# 4-IN-OPTPO-4-OUT-B.net
KiCad netlist of a schematic drawn in EAGLE
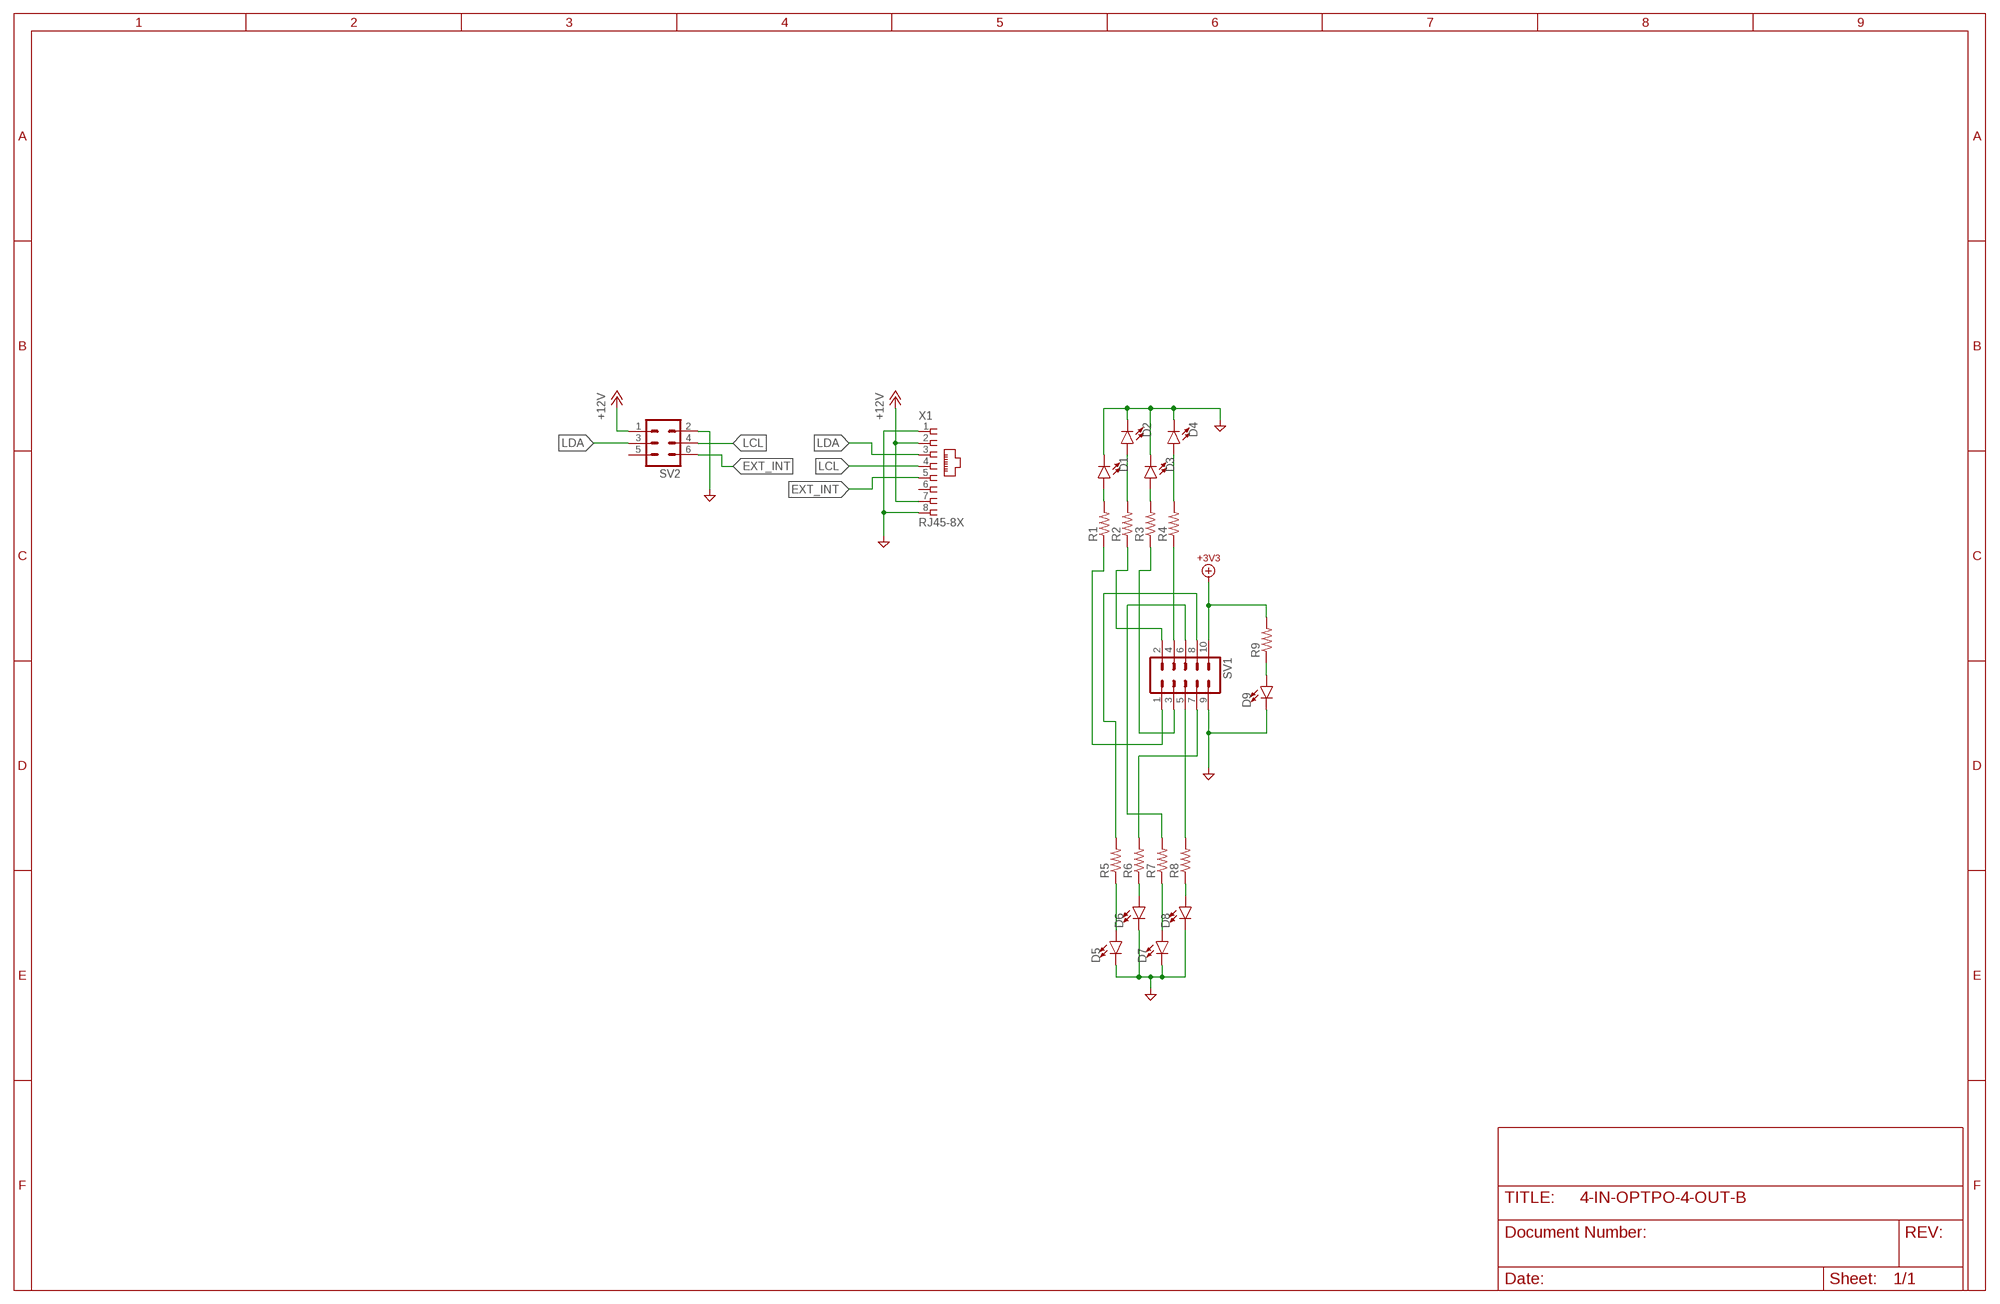
[diagram p0: schematic, sheet 1]

(export (version "E")
  (design (tool "Eeschema 10.0.6"))
  (components
    (comp (ref "D1")
      (value "LED3MM")
      (footprint "eagle-import:LED_3MM")
      (libsource (lib "eagle-import") (part "LED3MM"))
    )
    (comp (ref "D2")
      (value "LED3MM")
      (footprint "eagle-import:LED_3MM")
      (libsource (lib "eagle-import") (part "LED3MM"))
    )
    (comp (ref "D3")
      (value "LED3MM")
      (footprint "eagle-import:LED_3MM")
      (libsource (lib "eagle-import") (part "LED3MM"))
    )
    (comp (ref "D4")
      (value "LED3MM")
      (footprint "eagle-import:LED_3MM")
      (libsource (lib "eagle-import") (part "LED3MM"))
    )
    (comp (ref "D5")
      (value "LED3MM")
      (footprint "eagle-import:LED_3MM")
      (libsource (lib "eagle-import") (part "LED3MM"))
    )
    (comp (ref "D6")
      (value "LED3MM")
      (footprint "eagle-import:LED_3MM")
      (libsource (lib "eagle-import") (part "LED3MM"))
    )
    (comp (ref "D7")
      (value "LED3MM")
      (footprint "eagle-import:LED_3MM")
      (libsource (lib "eagle-import") (part "LED3MM"))
    )
    (comp (ref "D8")
      (value "LED3MM")
      (footprint "eagle-import:LED_3MM")
      (libsource (lib "eagle-import") (part "LED3MM"))
    )
    (comp (ref "D9")
      (value "LED3MM")
      (footprint "eagle-import:LED_3MM")
      (libsource (lib "eagle-import") (part "LED3MM"))
    )
    (comp (ref "R1")
      (value "R-US_R0805")
      (footprint "eagle-import:R0805")
      (libsource (lib "eagle-import") (part "R-US_R0805"))
    )
    (comp (ref "R2")
      (value "R-US_R0805")
      (footprint "eagle-import:R0805")
      (libsource (lib "eagle-import") (part "R-US_R0805"))
    )
    (comp (ref "R3")
      (value "R-US_R0805")
      (footprint "eagle-import:R0805")
      (libsource (lib "eagle-import") (part "R-US_R0805"))
    )
    (comp (ref "R4")
      (value "R-US_R0805")
      (footprint "eagle-import:R0805")
      (libsource (lib "eagle-import") (part "R-US_R0805"))
    )
    (comp (ref "R5")
      (value "R-US_R0805")
      (footprint "eagle-import:R0805")
      (libsource (lib "eagle-import") (part "R-US_R0805"))
    )
    (comp (ref "R6")
      (value "R-US_R0805")
      (footprint "eagle-import:R0805")
      (libsource (lib "eagle-import") (part "R-US_R0805"))
    )
    (comp (ref "R7")
      (value "R-US_R0805")
      (footprint "eagle-import:R0805")
      (libsource (lib "eagle-import") (part "R-US_R0805"))
    )
    (comp (ref "R8")
      (value "R-US_R0805")
      (footprint "eagle-import:R0805")
      (libsource (lib "eagle-import") (part "R-US_R0805"))
    )
    (comp (ref "R9")
      (value "R-US_R0805")
      (footprint "eagle-import:R0805")
      (libsource (lib "eagle-import") (part "R-US_R0805"))
    )
    (comp (ref "SV1")
      (value "ML10")
      (footprint "eagle-import:ML10")
      (libsource (lib "eagle-import") (part "ML10"))
    )
    (comp (ref "SV2")
      (value "ML6")
      (footprint "eagle-import:ML6")
      (libsource (lib "eagle-import") (part "ML6"))
    )
    (comp (ref "X1")
      (value "RJ45-8X")
      (footprint "eagle-import:RJ45-NO-SHIELD")
      (libsource (lib "eagle-import") (part "RJ45-8X"))
    )
  )
  (nets
    (net (code "1") (name "+12V") (class "Default")
      (node (ref "SV2") (pin "1") (pinfunction "1_1") (pintype "passive"))
      (node (ref "X1") (pin "2") (pinfunction "2_2") (pintype "passive"))
      (node (ref "X1") (pin "7") (pinfunction "7_7") (pintype "passive"))
    )
    (net (code "2") (name "EXT_INT") (class "Default")
      (node (ref "SV2") (pin "6") (pinfunction "6_6") (pintype "passive"))
      (node (ref "X1") (pin "5") (pinfunction "5_5") (pintype "passive"))
    )
    (net (code "3") (name "LCL") (class "Default")
      (node (ref "SV2") (pin "4") (pinfunction "4_4") (pintype "passive"))
      (node (ref "X1") (pin "4") (pinfunction "4_4") (pintype "passive"))
    )
    (net (code "4") (name "LDA") (class "Default")
      (node (ref "SV2") (pin "3") (pinfunction "3_3") (pintype "passive"))
      (node (ref "X1") (pin "3") (pinfunction "3_3") (pintype "passive"))
    )
    (net (code "5") (name "Net-(D1-PadA)") (class "Default")
      (node (ref "D1") (pin "A") (pinfunction "A_A") (pintype "passive"))
      (node (ref "R1") (pin "2") (pinfunction "2_2") (pintype "passive"))
    )
    (net (code "6") (name "Net-(D2-PadA)") (class "Default")
      (node (ref "D2") (pin "A") (pinfunction "A_A") (pintype "passive"))
      (node (ref "R2") (pin "2") (pinfunction "2_2") (pintype "passive"))
    )
    (net (code "7") (name "Net-(D3-PadA)") (class "Default")
      (node (ref "D3") (pin "A") (pinfunction "A_A") (pintype "passive"))
      (node (ref "R3") (pin "2") (pinfunction "2_2") (pintype "passive"))
    )
    (net (code "8") (name "Net-(D4-PadA)") (class "Default")
      (node (ref "D4") (pin "A") (pinfunction "A_A") (pintype "passive"))
      (node (ref "R4") (pin "2") (pinfunction "2_2") (pintype "passive"))
    )
    (net (code "9") (name "Net-(D5-PadA)") (class "Default")
      (node (ref "D5") (pin "A") (pinfunction "A_A") (pintype "passive"))
      (node (ref "R5") (pin "1") (pinfunction "1_1") (pintype "passive"))
    )
    (net (code "10") (name "Net-(D6-PadA)") (class "Default")
      (node (ref "D6") (pin "A") (pinfunction "A_A") (pintype "passive"))
      (node (ref "R6") (pin "1") (pinfunction "1_1") (pintype "passive"))
    )
    (net (code "11") (name "Net-(D7-PadA)") (class "Default")
      (node (ref "D7") (pin "A") (pinfunction "A_A") (pintype "passive"))
      (node (ref "R7") (pin "1") (pinfunction "1_1") (pintype "passive"))
    )
    (net (code "12") (name "Net-(D8-PadA)") (class "Default")
      (node (ref "D8") (pin "A") (pinfunction "A_A") (pintype "passive"))
      (node (ref "R8") (pin "1") (pinfunction "1_1") (pintype "passive"))
    )
    (net (code "13") (name "Net-(D9-PadA)") (class "Default")
      (node (ref "D9") (pin "A") (pinfunction "A_A") (pintype "passive"))
      (node (ref "R9") (pin "1") (pinfunction "1_1") (pintype "passive"))
    )
    (net (code "14") (name "Net-(R1-Pad1)") (class "Default")
      (node (ref "R1") (pin "1") (pinfunction "1_1") (pintype "passive"))
      (node (ref "SV1") (pin "1") (pinfunction "1_1") (pintype "passive"))
    )
    (net (code "15") (name "Net-(R2-Pad1)") (class "Default")
      (node (ref "R2") (pin "1") (pinfunction "1_1") (pintype "passive"))
      (node (ref "SV1") (pin "2") (pinfunction "2_2") (pintype "passive"))
    )
    (net (code "16") (name "Net-(R3-Pad1)") (class "Default")
      (node (ref "R3") (pin "1") (pinfunction "1_1") (pintype "passive"))
      (node (ref "SV1") (pin "3") (pinfunction "3_3") (pintype "passive"))
    )
    (net (code "17") (name "Net-(R4-Pad1)") (class "Default")
      (node (ref "R4") (pin "1") (pinfunction "1_1") (pintype "passive"))
      (node (ref "SV1") (pin "4") (pinfunction "4_4") (pintype "passive"))
    )
    (net (code "18") (name "Net-(R5-Pad2)") (class "Default")
      (node (ref "R5") (pin "2") (pinfunction "2_2") (pintype "passive"))
      (node (ref "SV1") (pin "8") (pinfunction "8_8") (pintype "passive"))
    )
    (net (code "19") (name "Net-(R6-Pad2)") (class "Default")
      (node (ref "R6") (pin "2") (pinfunction "2_2") (pintype "passive"))
      (node (ref "SV1") (pin "7") (pinfunction "7_7") (pintype "passive"))
    )
    (net (code "20") (name "Net-(R7-Pad2)") (class "Default")
      (node (ref "R7") (pin "2") (pinfunction "2_2") (pintype "passive"))
      (node (ref "SV1") (pin "6") (pinfunction "6_6") (pintype "passive"))
    )
    (net (code "21") (name "Net-(R8-Pad2)") (class "Default")
      (node (ref "R8") (pin "2") (pinfunction "2_2") (pintype "passive"))
      (node (ref "SV1") (pin "5") (pinfunction "5_5") (pintype "passive"))
    )
    (net (code "22") (name "V+3V3") (class "Default")
      (node (ref "R9") (pin "2") (pinfunction "2_2") (pintype "passive"))
      (node (ref "SV1") (pin "10") (pinfunction "10_10") (pintype "passive"))
    )
    (net (code "23") (name "VDG") (class "Default")
      (node (ref "D1") (pin "K") (pinfunction "C_K") (pintype "passive"))
      (node (ref "D2") (pin "K") (pinfunction "C_K") (pintype "passive"))
      (node (ref "D3") (pin "K") (pinfunction "C_K") (pintype "passive"))
      (node (ref "D4") (pin "K") (pinfunction "C_K") (pintype "passive"))
      (node (ref "D5") (pin "K") (pinfunction "C_K") (pintype "passive"))
      (node (ref "D6") (pin "K") (pinfunction "C_K") (pintype "passive"))
      (node (ref "D7") (pin "K") (pinfunction "C_K") (pintype "passive"))
      (node (ref "D8") (pin "K") (pinfunction "C_K") (pintype "passive"))
      (node (ref "D9") (pin "K") (pinfunction "C_K") (pintype "passive"))
      (node (ref "SV1") (pin "9") (pinfunction "9_9") (pintype "passive"))
      (node (ref "SV2") (pin "2") (pinfunction "2_2") (pintype "passive"))
      (node (ref "X1") (pin "1") (pinfunction "1_1") (pintype "passive"))
      (node (ref "X1") (pin "8") (pinfunction "8_8") (pintype "passive"))
    )
    (net (code "24") (name "unconnected-(SV2-Pad5)") (class "Default")
      (node (ref "SV2") (pin "5") (pinfunction "5_5") (pintype "passive"))
    )
    (net (code "25") (name "unconnected-(X1-Pad6)") (class "Default")
      (node (ref "X1") (pin "6") (pinfunction "6_6") (pintype "passive"))
    )
  )
)
